# MCU.net
KiCad netlist of a schematic drawn in Altium Designer
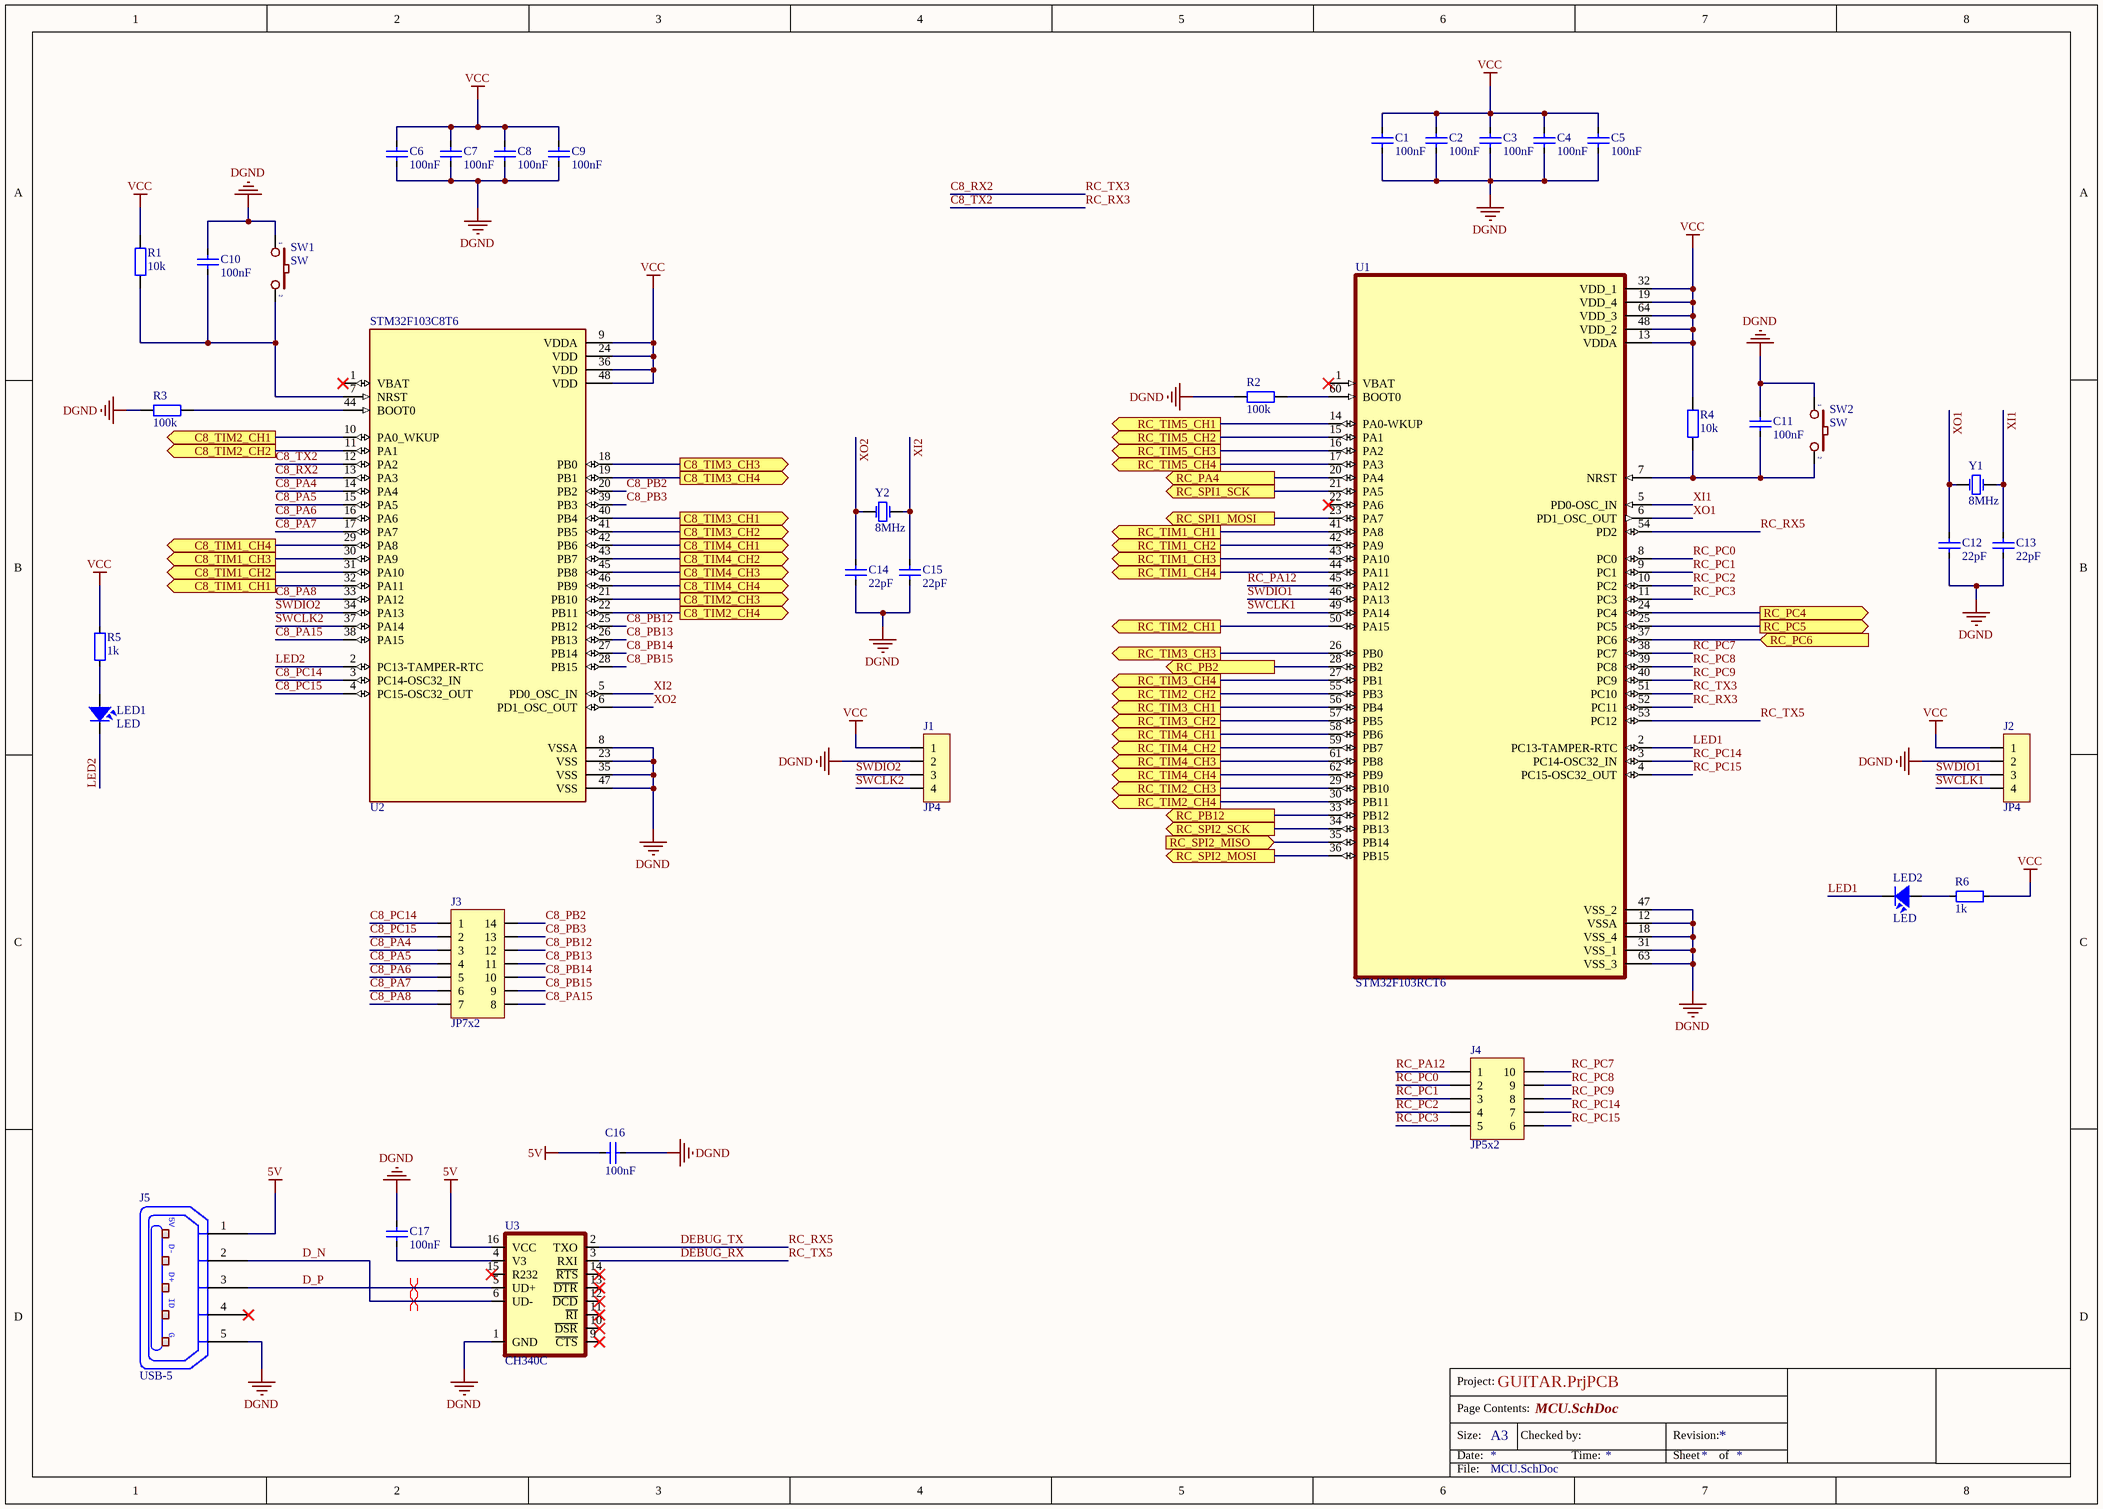
[diagram p0: MCU.SchDoc]

(export (version "E")
  (design (tool "Eeschema 10.0.6"))
  (components
    (comp (ref "C1")
      (value "100nF")
      (footprint "CAP_0805")
      (description "Capacitor")
      (fields (field (name "PUBLISHER") "Altium Limited"))
      (libsource (lib "My Library") (part "CapSMD"))
    )
    (comp (ref "C2")
      (value "100nF")
      (footprint "CAP_0805")
      (description "Capacitor")
      (fields (field (name "PUBLISHER") "Altium Limited"))
      (libsource (lib "My Library") (part "CapSMD"))
    )
    (comp (ref "C3")
      (value "100nF")
      (footprint "CAP_0805")
      (description "Capacitor")
      (fields (field (name "PUBLISHER") "Altium Limited"))
      (libsource (lib "My Library") (part "CapSMD"))
    )
    (comp (ref "C4")
      (value "100nF")
      (footprint "CAP_0805")
      (description "Capacitor")
      (fields (field (name "PUBLISHER") "Altium Limited"))
      (libsource (lib "My Library") (part "CapSMD"))
    )
    (comp (ref "C5")
      (value "100nF")
      (footprint "CAP_0805")
      (description "Capacitor")
      (fields (field (name "PUBLISHER") "Altium Limited"))
      (libsource (lib "My Library") (part "CapSMD"))
    )
    (comp (ref "C6")
      (value "100nF")
      (footprint "CAP_0805")
      (description "Capacitor")
      (fields (field (name "PUBLISHER") "Altium Limited"))
      (libsource (lib "My Library") (part "CapSMD"))
    )
    (comp (ref "C7")
      (value "100nF")
      (footprint "CAP_0805")
      (description "Capacitor")
      (fields (field (name "PUBLISHER") "Altium Limited"))
      (libsource (lib "My Library") (part "CapSMD"))
    )
    (comp (ref "C8")
      (value "100nF")
      (footprint "CAP_0805")
      (description "Capacitor")
      (fields (field (name "PUBLISHER") "Altium Limited"))
      (libsource (lib "My Library") (part "CapSMD"))
    )
    (comp (ref "C9")
      (value "100nF")
      (footprint "CAP_0805")
      (description "Capacitor")
      (fields (field (name "PUBLISHER") "Altium Limited"))
      (libsource (lib "My Library") (part "CapSMD"))
    )
    (comp (ref "C10")
      (value "100nF")
      (footprint "CAP_0805")
      (description "Capacitor")
      (fields (field (name "PUBLISHER") "Altium Limited"))
      (libsource (lib "My Library") (part "CapSMD"))
    )
    (comp (ref "C11")
      (value "100nF")
      (footprint "CAP_0805")
      (description "Capacitor")
      (fields (field (name "PUBLISHER") "Altium Limited"))
      (libsource (lib "My Library") (part "CapSMD"))
    )
    (comp (ref "C12")
      (value "22pF")
      (footprint "CAP_0805")
      (description "Capacitor")
      (fields (field (name "PUBLISHER") "Altium Limited"))
      (libsource (lib "My Library") (part "CapSMD"))
    )
    (comp (ref "C13")
      (value "22pF")
      (footprint "CAP_0805")
      (description "Capacitor")
      (fields (field (name "PUBLISHER") "Altium Limited"))
      (libsource (lib "My Library") (part "CapSMD"))
    )
    (comp (ref "C14")
      (value "22pF")
      (footprint "CAP_0805")
      (description "Capacitor")
      (fields (field (name "PUBLISHER") "Altium Limited"))
      (libsource (lib "My Library") (part "CapSMD"))
    )
    (comp (ref "C15")
      (value "22pF")
      (footprint "CAP_0805")
      (description "Capacitor")
      (fields (field (name "PUBLISHER") "Altium Limited"))
      (libsource (lib "My Library") (part "CapSMD"))
    )
    (comp (ref "C16")
      (value "100nF")
      (footprint "CAP_0805")
      (description "Capacitor")
      (fields (field (name "PUBLISHER") "Altium Limited"))
      (libsource (lib "My Library") (part "CapSMD"))
    )
    (comp (ref "C17")
      (value "100nF")
      (footprint "CAP_0805")
      (description "Capacitor")
      (fields (field (name "PUBLISHER") "Altium Limited"))
      (libsource (lib "My Library") (part "CapSMD"))
    )
    (comp (ref "J1")
      (value "JP4")
      (footprint "JP4-C1T")
      (description "WR-PHD 2.54 mm Angled Socket Header")
      (fields
        (field (name "MANUFACTURER") "Würth Elektronik eiSos GmbH")
        (field (name "PARTNO") "613004143121")
        (field (name "CREATED BY") "Karrer Zheng")
      )
      (libsource (lib "My Library") (part "JP4"))
    )
    (comp (ref "J2")
      (value "JP4")
      (footprint "JP4-C1T")
      (description "WR-PHD 2.54 mm Angled Socket Header")
      (fields
        (field (name "MANUFACTURER") "Würth Elektronik eiSos GmbH")
        (field (name "PARTNO") "613004143121")
        (field (name "CREATED BY") "Karrer Zheng")
      )
      (libsource (lib "My Library") (part "JP4"))
    )
    (comp (ref "J3")
      (value "JP7x2")
      (footprint "JP7-D2T")
      (description "WR-PHD 2.54 mm Dual Socket Header")
      (fields
        (field (name "MANUFACTURER") "Würth Elektronik eiSos GmbH")
        (field (name "PARTNO") "61301421821")
        (field (name "CREATED BY") "Karrer Zheng")
      )
      (libsource (lib "My Library") (part "JP7x2"))
    )
    (comp (ref "J4")
      (value "JP5x2")
      (footprint "JP5-D2T")
      (description "WR-PHD 2.54 mm Dual Socket Header")
      (fields
        (field (name "MANUFACTURER") "Würth Elektronik eiSos GmbH")
        (field (name "PARTNO") "61301021821")
        (field (name "CREATED BY") "Karrer Zheng")
      )
      (libsource (lib "My Library") (part "JP5x2"))
    )
    (comp (ref "J5")
      (value "USB-5")
      (footprint "USB-M1")
      (fields
        (field (name "MANUFACTURER") "FCI")
        (field (name "MANUFACTURER PART NUMBER") "10118193-0001LF")
        (field (name ".CREATOR") "MM")
        (field (name ".CHECKED PCB") "RF")
        (field (name ".CHECKED SCH") "MM")
      )
      (libsource (lib "My Library") (part "USB-5"))
    )
    (comp (ref "LED1")
      (value "LED")
      (footprint "LED-0805-Green")
      (description "LED Single colour Green and Red")
      (libsource (lib "My Library") (part "LED"))
    )
    (comp (ref "LED2")
      (value "LED")
      (footprint "LED-0805-Green")
      (description "LED Single colour Green and Red")
      (libsource (lib "My Library") (part "LED"))
    )
    (comp (ref "R1")
      (value "10k")
      (footprint "RES-SMD-0805")
      (description "Resistor SMD")
      (fields
        (field (name "MANUFACTURER") "Generic Components")
        (field (name "PUBLISHER") "Altium Hobart Technology Centre")
      )
      (libsource (lib "") (part "Resistor - SMD_1"))
    )
    (comp (ref "R2")
      (value "100k")
      (footprint "RES-SMD-0805")
      (description "Resistor SMD")
      (fields
        (field (name "MANUFACTURER") "Generic Components")
        (field (name "PUBLISHER") "Altium Hobart Technology Centre")
      )
      (libsource (lib "") (part "Resistor - SMD_1"))
    )
    (comp (ref "R3")
      (value "100k")
      (footprint "RES-SMD-0805")
      (description "Resistor SMD")
      (fields
        (field (name "MANUFACTURER") "Generic Components")
        (field (name "PUBLISHER") "Altium Hobart Technology Centre")
      )
      (libsource (lib "") (part "Resistor - SMD_1"))
    )
    (comp (ref "R4")
      (value "10k")
      (footprint "RES-SMD-0805")
      (description "Resistor SMD")
      (fields
        (field (name "MANUFACTURER") "Generic Components")
        (field (name "PUBLISHER") "Altium Hobart Technology Centre")
      )
      (libsource (lib "") (part "Resistor - SMD_1"))
    )
    (comp (ref "R5")
      (value "1k")
      (footprint "RES-SMD-0805")
      (description "Resistor")
      (fields
        (field (name "MANUFACTURER") "Generic Components")
        (field (name "PUBLISHER") "Altium Hobart Technology Centre")
      )
      (libsource (lib "My Library") (part "Resistor - SMD"))
    )
    (comp (ref "R6")
      (value "1k")
      (footprint "RES-SMD-0805")
      (description "Resistor")
      (fields
        (field (name "MANUFACTURER") "Generic Components")
        (field (name "PUBLISHER") "Altium Hobart Technology Centre")
      )
      (libsource (lib "My Library") (part "Resistor - SMD"))
    )
    (comp (ref "SW1")
      (value "SW")
      (footprint "SW 3x2x4")
      (description "Switch button 2 pin")
      (libsource (lib "My Library") (part "SW2"))
    )
    (comp (ref "SW2")
      (value "SW")
      (footprint "SW 3x2x4")
      (description "Switch button 2 pin")
      (libsource (lib "My Library") (part "SW2"))
    )
    (comp (ref "U1")
      (value "STM32F103RCT6")
      (footprint "QFP50P1200X1200X160-64N")
      (description "STM32 ARM-based 32-bit MCU 72MHz 256KB")
      (libsource (lib "My Library") (part "STM32F103RCT6"))
    )
    (comp (ref "U2")
      (value "STM32F103C8T6")
      (footprint "LQFP 48")
      (description "STM32 ARM-based 32-bit MCU with 64 Kbytes Flash, 64-pin LQFP, Industrial Temperature")
      (libsource (lib "My Library") (part "STM32F103C8T6"))
    )
    (comp (ref "U3")
      (value "CH340C")
      (footprint "SO016")
      (description "USB to serial chip CH340")
      (fields (field (name "MF") "WCH"))
      (libsource (lib "My Library") (part "CH340C"))
    )
    (comp (ref "Y1")
      (value "8MHz")
      (footprint "XTAL 5032 SMD")
      (description "Crystal Oscillator")
      (fields (field (name "PUBLISHER") "Altium Limited"))
      (libsource (lib "My Library") (part "XTAL"))
    )
    (comp (ref "Y2")
      (value "8MHz")
      (footprint "XTAL 5032 SMD")
      (description "Crystal Oscillator")
      (fields (field (name "PUBLISHER") "Altium Limited"))
      (libsource (lib "My Library") (part "XTAL"))
    )
  )
  (nets
    (net (code "1") (name "/C8_PA4") (class "Default")
      (node (ref "J3") (pin "3") (pinfunction "3_3") (pintype "passive"))
      (node (ref "U2") (pin "14") (pinfunction "PA4_14") (pintype "bidirectional"))
    )
    (net (code "2") (name "/C8_PA5") (class "Default")
      (node (ref "J3") (pin "4") (pinfunction "4_4") (pintype "passive"))
      (node (ref "U2") (pin "15") (pinfunction "PA5_15") (pintype "bidirectional"))
    )
    (net (code "3") (name "/C8_PA6") (class "Default")
      (node (ref "J3") (pin "5") (pinfunction "5_5") (pintype "passive"))
      (node (ref "U2") (pin "16") (pinfunction "PA6_16") (pintype "bidirectional"))
    )
    (net (code "4") (name "/C8_PA7") (class "Default")
      (node (ref "J3") (pin "6") (pinfunction "6_6") (pintype "passive"))
      (node (ref "U2") (pin "17") (pinfunction "PA7_17") (pintype "bidirectional"))
    )
    (net (code "5") (name "/C8_PA8") (class "Default")
      (node (ref "J3") (pin "7") (pinfunction "7_7") (pintype "passive"))
      (node (ref "U2") (pin "33") (pinfunction "PA12_33") (pintype "bidirectional"))
    )
    (net (code "6") (name "/C8_PA15") (class "Default")
      (node (ref "J3") (pin "8") (pinfunction "8_8") (pintype "passive"))
      (node (ref "U2") (pin "38") (pinfunction "PA15_38") (pintype "bidirectional"))
    )
    (net (code "7") (name "/C8_PB2") (class "Default")
      (node (ref "J3") (pin "14") (pinfunction "14_14") (pintype "passive"))
      (node (ref "U2") (pin "20") (pinfunction "PB2_20") (pintype "bidirectional"))
    )
    (net (code "8") (name "/C8_PB3") (class "Default")
      (node (ref "J3") (pin "13") (pinfunction "13_13") (pintype "passive"))
      (node (ref "U2") (pin "39") (pinfunction "PB3_39") (pintype "bidirectional"))
    )
    (net (code "9") (name "/C8_PB12") (class "Default")
      (node (ref "J3") (pin "12") (pinfunction "12_12") (pintype "passive"))
      (node (ref "U2") (pin "25") (pinfunction "PB12_25") (pintype "bidirectional"))
    )
    (net (code "10") (name "/C8_PB13") (class "Default")
      (node (ref "J3") (pin "11") (pinfunction "11_11") (pintype "passive"))
      (node (ref "U2") (pin "26") (pinfunction "PB13_26") (pintype "bidirectional"))
    )
    (net (code "11") (name "/C8_PB14") (class "Default")
      (node (ref "J3") (pin "10") (pinfunction "10_10") (pintype "passive"))
      (node (ref "U2") (pin "27") (pinfunction "PB14_27") (pintype "bidirectional"))
    )
    (net (code "12") (name "/C8_PB15") (class "Default")
      (node (ref "J3") (pin "9") (pinfunction "9_9") (pintype "passive"))
      (node (ref "U2") (pin "28") (pinfunction "PB15_28") (pintype "bidirectional"))
    )
    (net (code "13") (name "/C8_PC14") (class "Default")
      (node (ref "J3") (pin "1") (pinfunction "1_1") (pintype "passive"))
      (node (ref "U2") (pin "3") (pinfunction "PC14-OSC32_IN_3") (pintype "bidirectional"))
    )
    (net (code "14") (name "/C8_PC15") (class "Default")
      (node (ref "J3") (pin "2") (pinfunction "2_2") (pintype "passive"))
      (node (ref "U2") (pin "4") (pinfunction "PC15-OSC32_OUT_4") (pintype "bidirectional"))
    )
    (net (code "15") (name "/C8_RX2") (class "Default")
      (node (ref "U1") (pin "51") (pinfunction "PC10_51") (pintype "bidirectional"))
      (node (ref "U2") (pin "13") (pinfunction "PA3_13") (pintype "bidirectional"))
    )
    (net (code "16") (name "/C8_TIM1_CH1") (class "Default")
      (node (ref "U2") (pin "32") (pinfunction "PA11_32") (pintype "bidirectional"))
    )
    (net (code "17") (name "/C8_TIM1_CH2") (class "Default")
      (node (ref "U2") (pin "31") (pinfunction "PA10_31") (pintype "bidirectional"))
    )
    (net (code "18") (name "/C8_TIM1_CH3") (class "Default")
      (node (ref "U2") (pin "30") (pinfunction "PA9_30") (pintype "bidirectional"))
    )
    (net (code "19") (name "/C8_TIM1_CH4") (class "Default")
      (node (ref "U2") (pin "29") (pinfunction "PA8_29") (pintype "bidirectional"))
    )
    (net (code "20") (name "/C8_TIM2_CH1") (class "Default")
      (node (ref "U2") (pin "10") (pinfunction "PA0_WKUP_10") (pintype "bidirectional"))
    )
    (net (code "21") (name "/C8_TIM2_CH2") (class "Default")
      (node (ref "U2") (pin "11") (pinfunction "PA1_11") (pintype "bidirectional"))
    )
    (net (code "22") (name "/C8_TIM2_CH3") (class "Default")
      (node (ref "U2") (pin "21") (pinfunction "PB10_21") (pintype "bidirectional"))
    )
    (net (code "23") (name "/C8_TIM2_CH4") (class "Default")
      (node (ref "U2") (pin "22") (pinfunction "PB11_22") (pintype "bidirectional"))
    )
    (net (code "24") (name "/C8_TIM3_CH1") (class "Default")
      (node (ref "U2") (pin "40") (pinfunction "PB4_40") (pintype "bidirectional"))
    )
    (net (code "25") (name "/C8_TIM3_CH2") (class "Default")
      (node (ref "U2") (pin "41") (pinfunction "PB5_41") (pintype "bidirectional"))
    )
    (net (code "26") (name "/C8_TIM3_CH3") (class "Default")
      (node (ref "U2") (pin "18") (pinfunction "PB0_18") (pintype "bidirectional"))
    )
    (net (code "27") (name "/C8_TIM3_CH4") (class "Default")
      (node (ref "U2") (pin "19") (pinfunction "PB1_19") (pintype "bidirectional"))
    )
    (net (code "28") (name "/C8_TIM4_CH1") (class "Default")
      (node (ref "U2") (pin "42") (pinfunction "PB6_42") (pintype "bidirectional"))
    )
    (net (code "29") (name "/C8_TIM4_CH2") (class "Default")
      (node (ref "U2") (pin "43") (pinfunction "PB7_43") (pintype "bidirectional"))
    )
    (net (code "30") (name "/C8_TIM4_CH3") (class "Default")
      (node (ref "U2") (pin "45") (pinfunction "PB8_45") (pintype "bidirectional"))
    )
    (net (code "31") (name "/C8_TIM4_CH4") (class "Default")
      (node (ref "U2") (pin "46") (pinfunction "PB9_46") (pintype "bidirectional"))
    )
    (net (code "32") (name "/C8_TX2") (class "Default")
      (node (ref "U1") (pin "52") (pinfunction "PC11_52") (pintype "bidirectional"))
      (node (ref "U2") (pin "12") (pinfunction "PA2_12") (pintype "bidirectional"))
    )
    (net (code "33") (name "/DEBUG_RX") (class "Default")
      (node (ref "U1") (pin "53") (pinfunction "PC12_53") (pintype "bidirectional"))
      (node (ref "U3") (pin "3") (pinfunction "RXI_3") (pintype "bidirectional"))
    )
    (net (code "34") (name "/DEBUG_TX") (class "Default")
      (node (ref "U1") (pin "54") (pinfunction "PD2_54") (pintype "bidirectional"))
      (node (ref "U3") (pin "2") (pinfunction "TXO_2") (pintype "bidirectional"))
    )
    (net (code "35") (name "/D_N") (class "Default")
      (node (ref "J5") (pin "2") (pinfunction "P2_2") (pintype "passive"))
      (node (ref "U3") (pin "6") (pinfunction "UD-_6") (pintype "bidirectional"))
    )
    (net (code "36") (name "/D_P") (class "Default")
      (node (ref "J5") (pin "3") (pinfunction "P3_3") (pintype "passive"))
      (node (ref "U3") (pin "5") (pinfunction "UD+_5") (pintype "bidirectional"))
    )
    (net (code "37") (name "/LED1") (class "Default")
      (node (ref "LED2") (pin "2") (pinfunction "2_2") (pintype "passive"))
      (node (ref "U1") (pin "2") (pinfunction "PC13-TAMPER-RTC_2") (pintype "bidirectional"))
    )
    (net (code "38") (name "/LED2") (class "Default")
      (node (ref "LED1") (pin "2") (pinfunction "2_2") (pintype "passive"))
      (node (ref "U2") (pin "2") (pinfunction "PC13-TAMPER-RTC_2") (pintype "bidirectional"))
    )
    (net (code "39") (name "/RC_PA4") (class "Default")
      (node (ref "U1") (pin "20") (pinfunction "PA4_20") (pintype "bidirectional"))
    )
    (net (code "40") (name "/RC_PA12") (class "Default")
      (node (ref "J4") (pin "1") (pinfunction "1_1") (pintype "passive"))
      (node (ref "U1") (pin "45") (pinfunction "PA12_45") (pintype "bidirectional"))
    )
    (net (code "41") (name "/RC_PB2") (class "Default")
      (node (ref "U1") (pin "28") (pinfunction "PB2_28") (pintype "bidirectional"))
    )
    (net (code "42") (name "/RC_PB12") (class "Default")
      (node (ref "U1") (pin "33") (pinfunction "PB12_33") (pintype "bidirectional"))
    )
    (net (code "43") (name "/RC_PC0") (class "Default")
      (node (ref "J4") (pin "2") (pinfunction "2_2") (pintype "passive"))
      (node (ref "U1") (pin "8") (pinfunction "PC0_8") (pintype "bidirectional"))
    )
    (net (code "44") (name "/RC_PC1") (class "Default")
      (node (ref "J4") (pin "3") (pinfunction "3_3") (pintype "passive"))
      (node (ref "U1") (pin "9") (pinfunction "PC1_9") (pintype "bidirectional"))
    )
    (net (code "45") (name "/RC_PC2") (class "Default")
      (node (ref "J4") (pin "4") (pinfunction "4_4") (pintype "passive"))
      (node (ref "U1") (pin "10") (pinfunction "PC2_10") (pintype "bidirectional"))
    )
    (net (code "46") (name "/RC_PC3") (class "Default")
      (node (ref "J4") (pin "5") (pinfunction "5_5") (pintype "passive"))
      (node (ref "U1") (pin "11") (pinfunction "PC3_11") (pintype "bidirectional"))
    )
    (net (code "47") (name "/RC_PC4") (class "Default")
      (node (ref "U1") (pin "24") (pinfunction "PC4_24") (pintype "bidirectional"))
    )
    (net (code "48") (name "/RC_PC5") (class "Default")
      (node (ref "U1") (pin "25") (pinfunction "PC5_25") (pintype "bidirectional"))
    )
    (net (code "49") (name "/RC_PC6") (class "Default")
      (node (ref "U1") (pin "37") (pinfunction "PC6_37") (pintype "bidirectional"))
    )
    (net (code "50") (name "/RC_PC7") (class "Default")
      (node (ref "J4") (pin "10") (pinfunction "10_10") (pintype "passive"))
      (node (ref "U1") (pin "38") (pinfunction "PC7_38") (pintype "bidirectional"))
    )
    (net (code "51") (name "/RC_PC8") (class "Default")
      (node (ref "J4") (pin "9") (pinfunction "9_9") (pintype "passive"))
      (node (ref "U1") (pin "39") (pinfunction "PC8_39") (pintype "bidirectional"))
    )
    (net (code "52") (name "/RC_PC9") (class "Default")
      (node (ref "J4") (pin "8") (pinfunction "8_8") (pintype "passive"))
      (node (ref "U1") (pin "40") (pinfunction "PC9_40") (pintype "bidirectional"))
    )
    (net (code "53") (name "/RC_PC14") (class "Default")
      (node (ref "J4") (pin "7") (pinfunction "7_7") (pintype "passive"))
      (node (ref "U1") (pin "3") (pinfunction "PC14-OSC32_IN_3") (pintype "bidirectional"))
    )
    (net (code "54") (name "/RC_PC15") (class "Default")
      (node (ref "J4") (pin "6") (pinfunction "6_6") (pintype "passive"))
      (node (ref "U1") (pin "4") (pinfunction "PC15-OSC32_OUT_4") (pintype "bidirectional"))
    )
    (net (code "55") (name "/RC_SPI1_MOSI") (class "Default")
      (node (ref "U1") (pin "23") (pinfunction "PA7_23") (pintype "bidirectional"))
    )
    (net (code "56") (name "/RC_SPI1_SCK") (class "Default")
      (node (ref "U1") (pin "21") (pinfunction "PA5_21") (pintype "bidirectional"))
    )
    (net (code "57") (name "/RC_SPI2_MISO") (class "Default")
      (node (ref "U1") (pin "35") (pinfunction "PB14_35") (pintype "bidirectional"))
    )
    (net (code "58") (name "/RC_SPI2_MOSI") (class "Default")
      (node (ref "U1") (pin "36") (pinfunction "PB15_36") (pintype "bidirectional"))
    )
    (net (code "59") (name "/RC_SPI2_SCK") (class "Default")
      (node (ref "U1") (pin "34") (pinfunction "PB13_34") (pintype "bidirectional"))
    )
    (net (code "60") (name "/RC_TIM1_CH1") (class "Default")
      (node (ref "U1") (pin "41") (pinfunction "PA8_41") (pintype "bidirectional"))
    )
    (net (code "61") (name "/RC_TIM1_CH2") (class "Default")
      (node (ref "U1") (pin "42") (pinfunction "PA9_42") (pintype "bidirectional"))
    )
    (net (code "62") (name "/RC_TIM1_CH3") (class "Default")
      (node (ref "U1") (pin "43") (pinfunction "PA10_43") (pintype "bidirectional"))
    )
    (net (code "63") (name "/RC_TIM1_CH4") (class "Default")
      (node (ref "U1") (pin "44") (pinfunction "PA11_44") (pintype "bidirectional"))
    )
    (net (code "64") (name "/RC_TIM2_CH1") (class "Default")
      (node (ref "U1") (pin "50") (pinfunction "PA15_50") (pintype "bidirectional"))
    )
    (net (code "65") (name "/RC_TIM2_CH2") (class "Default")
      (node (ref "U1") (pin "55") (pinfunction "PB3_55") (pintype "bidirectional"))
    )
    (net (code "66") (name "/RC_TIM2_CH3") (class "Default")
      (node (ref "U1") (pin "29") (pinfunction "PB10_29") (pintype "bidirectional"))
    )
    (net (code "67") (name "/RC_TIM2_CH4") (class "Default")
      (node (ref "U1") (pin "30") (pinfunction "PB11_30") (pintype "bidirectional"))
    )
    (net (code "68") (name "/RC_TIM3_CH1") (class "Default")
      (node (ref "U1") (pin "56") (pinfunction "PB4_56") (pintype "bidirectional"))
    )
    (net (code "69") (name "/RC_TIM3_CH2") (class "Default")
      (node (ref "U1") (pin "57") (pinfunction "PB5_57") (pintype "bidirectional"))
    )
    (net (code "70") (name "/RC_TIM3_CH3") (class "Default")
      (node (ref "U1") (pin "26") (pinfunction "PB0_26") (pintype "bidirectional"))
    )
    (net (code "71") (name "/RC_TIM3_CH4") (class "Default")
      (node (ref "U1") (pin "27") (pinfunction "PB1_27") (pintype "bidirectional"))
    )
    (net (code "72") (name "/RC_TIM4_CH1") (class "Default")
      (node (ref "U1") (pin "58") (pinfunction "PB6_58") (pintype "bidirectional"))
    )
    (net (code "73") (name "/RC_TIM4_CH2") (class "Default")
      (node (ref "U1") (pin "59") (pinfunction "PB7_59") (pintype "bidirectional"))
    )
    (net (code "74") (name "/RC_TIM4_CH3") (class "Default")
      (node (ref "U1") (pin "61") (pinfunction "PB8_61") (pintype "bidirectional"))
    )
    (net (code "75") (name "/RC_TIM4_CH4") (class "Default")
      (node (ref "U1") (pin "62") (pinfunction "PB9_62") (pintype "bidirectional"))
    )
    (net (code "76") (name "/RC_TIM5_CH1") (class "Default")
      (node (ref "U1") (pin "14") (pinfunction "PA0-WKUP_14") (pintype "bidirectional"))
    )
    (net (code "77") (name "/RC_TIM5_CH2") (class "Default")
      (node (ref "U1") (pin "15") (pinfunction "PA1_15") (pintype "bidirectional"))
    )
    (net (code "78") (name "/RC_TIM5_CH3") (class "Default")
      (node (ref "U1") (pin "16") (pinfunction "PA2_16") (pintype "bidirectional"))
    )
    (net (code "79") (name "/RC_TIM5_CH4") (class "Default")
      (node (ref "U1") (pin "17") (pinfunction "PA3_17") (pintype "bidirectional"))
    )
    (net (code "80") (name "/SWCLK1") (class "Default")
      (node (ref "J2") (pin "4") (pinfunction "4_4") (pintype "passive"))
      (node (ref "U1") (pin "49") (pinfunction "PA14_49") (pintype "bidirectional"))
    )
    (net (code "81") (name "/SWCLK2") (class "Default")
      (node (ref "J1") (pin "4") (pinfunction "4_4") (pintype "passive"))
      (node (ref "U2") (pin "37") (pinfunction "PA14_37") (pintype "bidirectional"))
    )
    (net (code "82") (name "/SWDIO1") (class "Default")
      (node (ref "J2") (pin "3") (pinfunction "3_3") (pintype "passive"))
      (node (ref "U1") (pin "46") (pinfunction "PA13_46") (pintype "bidirectional"))
    )
    (net (code "83") (name "/SWDIO2") (class "Default")
      (node (ref "J1") (pin "3") (pinfunction "3_3") (pintype "passive"))
      (node (ref "U2") (pin "34") (pinfunction "PA13_34") (pintype "bidirectional"))
    )
    (net (code "84") (name "/XI1") (class "Default")
      (node (ref "C13") (pin "2") (pinfunction "2_2") (pintype "passive"))
      (node (ref "U1") (pin "5") (pinfunction "PD0-OSC_IN_5") (pintype "input"))
      (node (ref "Y1") (pin "2") (pinfunction "OSC2_2") (pintype "passive"))
    )
    (net (code "85") (name "/XI2") (class "Default")
      (node (ref "C15") (pin "2") (pinfunction "2_2") (pintype "passive"))
      (node (ref "U2") (pin "5") (pinfunction "PD0_OSC_IN_5") (pintype "bidirectional"))
      (node (ref "Y2") (pin "2") (pinfunction "OSC2_2") (pintype "passive"))
    )
    (net (code "86") (name "/XO1") (class "Default")
      (node (ref "C12") (pin "2") (pinfunction "2_2") (pintype "passive"))
      (node (ref "U1") (pin "6") (pinfunction "PD1_OSC_OUT_6") (pintype "output"))
      (node (ref "Y1") (pin "1") (pinfunction "OSC1_1") (pintype "passive"))
    )
    (net (code "87") (name "/XO2") (class "Default")
      (node (ref "C14") (pin "2") (pinfunction "2_2") (pintype "passive"))
      (node (ref "U2") (pin "6") (pinfunction "PD1_OSC_OUT_6") (pintype "bidirectional"))
      (node (ref "Y2") (pin "1") (pinfunction "OSC1_1") (pintype "passive"))
    )
    (net (code "88") (name "5V") (class "Default")
      (node (ref "C16") (pin "2") (pinfunction "2_2") (pintype "passive"))
      (node (ref "J5") (pin "1") (pinfunction "P1_1") (pintype "passive"))
      (node (ref "U3") (pin "16") (pinfunction "VCC_16") (pintype "bidirectional"))
    )
    (net (code "89") (name "DGND") (class "Default")
      (node (ref "C1") (pin "2") (pinfunction "2_2") (pintype "passive"))
      (node (ref "C10") (pin "1") (pinfunction "1_1") (pintype "passive"))
      (node (ref "C11") (pin "1") (pinfunction "1_1") (pintype "passive"))
      (node (ref "C12") (pin "1") (pinfunction "1_1") (pintype "passive"))
      (node (ref "C13") (pin "1") (pinfunction "1_1") (pintype "passive"))
      (node (ref "C14") (pin "1") (pinfunction "1_1") (pintype "passive"))
      (node (ref "C15") (pin "1") (pinfunction "1_1") (pintype "passive"))
      (node (ref "C16") (pin "1") (pinfunction "1_1") (pintype "passive"))
      (node (ref "C17") (pin "2") (pinfunction "2_2") (pintype "passive"))
      (node (ref "C2") (pin "2") (pinfunction "2_2") (pintype "passive"))
      (node (ref "C3") (pin "2") (pinfunction "2_2") (pintype "passive"))
      (node (ref "C4") (pin "2") (pinfunction "2_2") (pintype "passive"))
      (node (ref "C5") (pin "2") (pinfunction "2_2") (pintype "passive"))
      (node (ref "C6") (pin "2") (pinfunction "2_2") (pintype "passive"))
      (node (ref "C7") (pin "2") (pinfunction "2_2") (pintype "passive"))
      (node (ref "C8") (pin "2") (pinfunction "2_2") (pintype "passive"))
      (node (ref "C9") (pin "2") (pinfunction "2_2") (pintype "passive"))
      (node (ref "J1") (pin "2") (pinfunction "2_2") (pintype "passive"))
      (node (ref "J2") (pin "2") (pinfunction "2_2") (pintype "passive"))
      (node (ref "J5") (pin "5") (pinfunction "P5_5") (pintype "passive"))
      (node (ref "R2") (pin "1") (pinfunction "1_1") (pintype "passive"))
      (node (ref "R3") (pin "1") (pinfunction "1_1") (pintype "passive"))
      (node (ref "SW1") (pin "1") (pinfunction "1_1") (pintype "passive"))
      (node (ref "SW2") (pin "1") (pinfunction "1_1") (pintype "passive"))
      (node (ref "U1") (pin "12") (pinfunction "VSSA_12") (pintype "power_in"))
      (node (ref "U1") (pin "18") (pinfunction "VSS_4_18") (pintype "power_in"))
      (node (ref "U1") (pin "31") (pinfunction "VSS_1_31") (pintype "power_in"))
      (node (ref "U1") (pin "47") (pinfunction "VSS_2_47") (pintype "power_in"))
      (node (ref "U1") (pin "63") (pinfunction "VSS_3_63") (pintype "power_in"))
      (node (ref "U2") (pin "23") (pinfunction "VSS_23") (pintype "power_in"))
      (node (ref "U2") (pin "35") (pinfunction "VSS_35") (pintype "power_in"))
      (node (ref "U2") (pin "47") (pinfunction "VSS_47") (pintype "power_in"))
      (node (ref "U2") (pin "8") (pinfunction "VSSA_8") (pintype "power_in"))
      (node (ref "U3") (pin "1") (pinfunction "GND_1") (pintype "bidirectional"))
    )
    (net (code "90") (name "Net-(LED1-Pad1)") (class "Default")
      (node (ref "LED1") (pin "1") (pinfunction "1_1") (pintype "passive"))
      (node (ref "R5") (pin "2") (pinfunction "2_2") (pintype "passive"))
    )
    (net (code "91") (name "Net-(LED2-Pad1)") (class "Default")
      (node (ref "LED2") (pin "1") (pinfunction "1_1") (pintype "passive"))
      (node (ref "R6") (pin "2") (pinfunction "2_2") (pintype "passive"))
    )
    (net (code "92") (name "Net-(U1-BOOT0)") (class "Default")
      (node (ref "R2") (pin "2") (pinfunction "2_2") (pintype "passive"))
      (node (ref "U1") (pin "60") (pinfunction "BOOT0_60") (pintype "input"))
    )
    (net (code "93") (name "Net-(U1-NRST)") (class "Default")
      (node (ref "C11") (pin "2") (pinfunction "2_2") (pintype "passive"))
      (node (ref "R4") (pin "2") (pinfunction "2_2") (pintype "passive"))
      (node (ref "SW2") (pin "2") (pinfunction "2_2") (pintype "passive"))
      (node (ref "U1") (pin "7") (pinfunction "NRST_7") (pintype "input"))
    )
    (net (code "94") (name "Net-(U2-BOOT0)") (class "Default")
      (node (ref "R3") (pin "2") (pinfunction "2_2") (pintype "passive"))
      (node (ref "U2") (pin "44") (pinfunction "BOOT0_44") (pintype "input"))
    )
    (net (code "95") (name "Net-(U2-NRST)") (class "Default")
      (node (ref "C10") (pin "2") (pinfunction "2_2") (pintype "passive"))
      (node (ref "R1") (pin "2") (pinfunction "2_2") (pintype "passive"))
      (node (ref "SW1") (pin "2") (pinfunction "2_2") (pintype "passive"))
      (node (ref "U2") (pin "7") (pinfunction "NRST_7") (pintype "input"))
    )
    (net (code "96") (name "Net-(U3-V3)") (class "Default")
      (node (ref "C17") (pin "1") (pinfunction "1_1") (pintype "passive"))
      (node (ref "U3") (pin "4") (pinfunction "V3_4") (pintype "bidirectional"))
    )
    (net (code "97") (name "VCC") (class "Default")
      (node (ref "C1") (pin "1") (pinfunction "1_1") (pintype "passive"))
      (node (ref "C2") (pin "1") (pinfunction "1_1") (pintype "passive"))
      (node (ref "C3") (pin "1") (pinfunction "1_1") (pintype "passive"))
      (node (ref "C4") (pin "1") (pinfunction "1_1") (pintype "passive"))
      (node (ref "C5") (pin "1") (pinfunction "1_1") (pintype "passive"))
      (node (ref "C6") (pin "1") (pinfunction "1_1") (pintype "passive"))
      (node (ref "C7") (pin "1") (pinfunction "1_1") (pintype "passive"))
      (node (ref "C8") (pin "1") (pinfunction "1_1") (pintype "passive"))
      (node (ref "C9") (pin "1") (pinfunction "1_1") (pintype "passive"))
      (node (ref "J1") (pin "1") (pinfunction "1_1") (pintype "passive"))
      (node (ref "J2") (pin "1") (pinfunction "1_1") (pintype "passive"))
      (node (ref "R1") (pin "1") (pinfunction "1_1") (pintype "passive"))
      (node (ref "R4") (pin "1") (pinfunction "1_1") (pintype "passive"))
      (node (ref "R5") (pin "1") (pinfunction "1_1") (pintype "passive"))
      (node (ref "R6") (pin "1") (pinfunction "1_1") (pintype "passive"))
      (node (ref "U1") (pin "13") (pinfunction "VDDA_13") (pintype "power_in"))
      (node (ref "U1") (pin "19") (pinfunction "VDD_4_19") (pintype "power_in"))
      (node (ref "U1") (pin "32") (pinfunction "VDD_1_32") (pintype "power_in"))
      (node (ref "U1") (pin "48") (pinfunction "VDD_2_48") (pintype "power_in"))
      (node (ref "U1") (pin "64") (pinfunction "VDD_3_64") (pintype "power_in"))
      (node (ref "U2") (pin "24") (pinfunction "VDD_24") (pintype "power_in"))
      (node (ref "U2") (pin "36") (pinfunction "VDD_36") (pintype "power_in"))
      (node (ref "U2") (pin "48") (pinfunction "VDD_48") (pintype "power_in"))
      (node (ref "U2") (pin "9") (pinfunction "VDDA_9") (pintype "power_in"))
    )
    (net (code "98") (name "unconnected-(J5-P4-Pad4)") (class "Default")
      (node (ref "J5") (pin "4") (pinfunction "P4_4") (pintype "passive+no_connect"))
    )
    (net (code "99") (name "unconnected-(U1-PA6-Pad22)") (class "Default")
      (node (ref "U1") (pin "22") (pinfunction "PA6_22") (pintype "bidirectional+no_connect"))
    )
    (net (code "100") (name "unconnected-(U1-VBAT-Pad1)") (class "Default")
      (node (ref "U1") (pin "1") (pinfunction "VBAT_1") (pintype "input+no_connect"))
    )
    (net (code "101") (name "unconnected-(U2-VBAT-Pad1)") (class "Default")
      (node (ref "U2") (pin "1") (pinfunction "VBAT_1") (pintype "bidirectional+no_connect"))
    )
    (net (code "102") (name "unconnected-(U3-R232-Pad15)") (class "Default")
      (node (ref "U3") (pin "15") (pinfunction "R232_15") (pintype "bidirectional+no_connect"))
    )
    (net (code "103") (name "unconnected-(U3-~{CTS}-Pad9)") (class "Default")
      (node (ref "U3") (pin "9") (pinfunction "~{CTS}_9") (pintype "bidirectional+no_connect"))
    )
    (net (code "104") (name "unconnected-(U3-~{DCD}-Pad12)") (class "Default")
      (node (ref "U3") (pin "12") (pinfunction "~{DCD}_12") (pintype "bidirectional+no_connect"))
    )
    (net (code "105") (name "unconnected-(U3-~{DSR}-Pad10)") (class "Default")
      (node (ref "U3") (pin "10") (pinfunction "~{DSR}_10") (pintype "bidirectional+no_connect"))
    )
    (net (code "106") (name "unconnected-(U3-~{DTR}-Pad13)") (class "Default")
      (node (ref "U3") (pin "13") (pinfunction "~{DTR}_13") (pintype "bidirectional+no_connect"))
    )
    (net (code "107") (name "unconnected-(U3-~{RI}-Pad11)") (class "Default")
      (node (ref "U3") (pin "11") (pinfunction "~{RI}_11") (pintype "bidirectional+no_connect"))
    )
    (net (code "108") (name "unconnected-(U3-~{RTS}-Pad14)") (class "Default")
      (node (ref "U3") (pin "14") (pinfunction "~{RTS}_14") (pintype "bidirectional+no_connect"))
    )
  )
)
